# lcdInterface.net
KiCad netlist of a schematic drawn in EAGLE
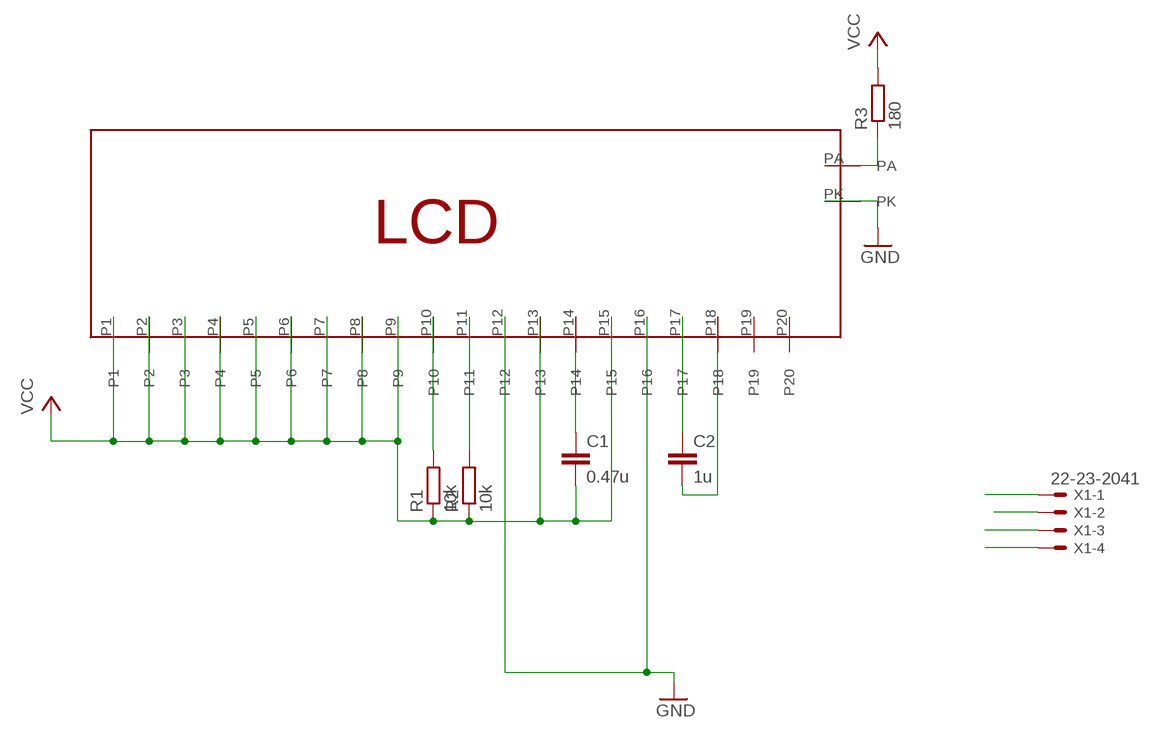
[diagram p0: schematic, sheet 1]

(export (version "E")
  (design (tool "Eeschema 10.0.6"))
  (components
    (comp (ref "C1")
      (value "0.47u")
      (footprint "eagle-import:C050-055X075")
      (libsource (lib "eagle-import") (part "C-EU050-055X075"))
    )
    (comp (ref "C2")
      (value "1u")
      (footprint "eagle-import:C050-030X075")
      (libsource (lib "eagle-import") (part "C-EU050-030X075"))
    )
    (comp (ref "R1")
      (value "10k")
      (footprint "eagle-import:0207_10")
      (libsource (lib "eagle-import") (part "R-EU_0207/10"))
    )
    (comp (ref "R2")
      (value "10k")
      (footprint "eagle-import:0207_10")
      (libsource (lib "eagle-import") (part "R-EU_0207/10"))
    )
    (comp (ref "R3")
      (value "180")
      (footprint "eagle-import:0207_10")
      (libsource (lib "eagle-import") (part "R-EU_0207/10"))
    )
    (comp (ref "U$1")
      (value "GE-01602F")
      (footprint "eagle-import:GE01602F")
      (libsource (lib "eagle-import") (part "GE-01602F"))
    )
    (comp (ref "X1")
      (value "22-23-2041")
      (footprint "eagle-import:22-23-2041")
      (fields (field (name "MF") "MOLEX"))
      (libsource (lib "eagle-import") (part "22-23-2041"))
    )
  )
  (nets
    (net (code "1") (name "/SCL") (class "Default")
      (node (ref "R1") (pin "2") (pinfunction "2_2") (pintype "passive"))
      (node (ref "U$1") (pin "P10") (pinfunction "P10_P10") (pintype "bidirectional"))
      (node (ref "X1") (pin "1") (pinfunction "S_1") (pintype "passive"))
    )
    (net (code "2") (name "/SDA") (class "Default")
      (node (ref "R2") (pin "2") (pinfunction "2_2") (pintype "passive"))
      (node (ref "U$1") (pin "P11") (pinfunction "P11_P11") (pintype "bidirectional"))
      (node (ref "X1") (pin "2") (pinfunction "S_2") (pintype "passive"))
    )
    (net (code "3") (name "GND") (class "Default")
      (node (ref "U$1") (pin "P12") (pinfunction "P12_P12") (pintype "bidirectional"))
      (node (ref "U$1") (pin "P16") (pinfunction "P16_P16") (pintype "bidirectional"))
      (node (ref "U$1") (pin "PK") (pinfunction "PK_PK") (pintype "bidirectional"))
      (node (ref "X1") (pin "4") (pinfunction "S_4") (pintype "passive"))
    )
    (net (code "4") (name "Net-(C1-Pad1)") (class "Default")
      (node (ref "C1") (pin "1") (pinfunction "1_1") (pintype "passive"))
      (node (ref "U$1") (pin "P14") (pinfunction "P14_P14") (pintype "bidirectional"))
    )
    (net (code "5") (name "Net-(C2-Pad1)") (class "Default")
      (node (ref "C2") (pin "1") (pinfunction "1_1") (pintype "passive"))
      (node (ref "U$1") (pin "P17") (pinfunction "P17_P17") (pintype "bidirectional"))
    )
    (net (code "6") (name "Net-(C2-Pad2)") (class "Default")
      (node (ref "C2") (pin "2") (pinfunction "2_2") (pintype "passive"))
      (node (ref "U$1") (pin "P18") (pinfunction "P18_P18") (pintype "bidirectional"))
    )
    (net (code "7") (name "Net-(R3-Pad1)") (class "Default")
      (node (ref "R3") (pin "1") (pinfunction "1_1") (pintype "passive"))
      (node (ref "U$1") (pin "PA") (pinfunction "PA_PA") (pintype "bidirectional"))
    )
    (net (code "8") (name "VCC") (class "Default")
      (node (ref "C1") (pin "2") (pinfunction "2_2") (pintype "passive"))
      (node (ref "R1") (pin "1") (pinfunction "1_1") (pintype "passive"))
      (node (ref "R2") (pin "1") (pinfunction "1_1") (pintype "passive"))
      (node (ref "R3") (pin "2") (pinfunction "2_2") (pintype "passive"))
      (node (ref "U$1") (pin "P1") (pinfunction "P1_P1") (pintype "bidirectional"))
      (node (ref "U$1") (pin "P13") (pinfunction "P13_P13") (pintype "bidirectional"))
      (node (ref "U$1") (pin "P15") (pinfunction "P15_P15") (pintype "bidirectional"))
      (node (ref "U$1") (pin "P2") (pinfunction "P2_P2") (pintype "bidirectional"))
      (node (ref "U$1") (pin "P3") (pinfunction "P3_P3") (pintype "bidirectional"))
      (node (ref "U$1") (pin "P4") (pinfunction "P4_P4") (pintype "bidirectional"))
      (node (ref "U$1") (pin "P5") (pinfunction "P5_P5") (pintype "bidirectional"))
      (node (ref "U$1") (pin "P6") (pinfunction "P6_P6") (pintype "bidirectional"))
      (node (ref "U$1") (pin "P7") (pinfunction "P7_P7") (pintype "bidirectional"))
      (node (ref "U$1") (pin "P8") (pinfunction "P8_P8") (pintype "bidirectional"))
      (node (ref "U$1") (pin "P9") (pinfunction "P9_P9") (pintype "bidirectional"))
      (node (ref "X1") (pin "3") (pinfunction "S_3") (pintype "passive"))
    )
    (net (code "9") (name "unconnected-(U$1-PadP19)") (class "Default")
      (node (ref "U$1") (pin "P19") (pinfunction "P19_P19") (pintype "bidirectional"))
    )
    (net (code "10") (name "unconnected-(U$1-PadP20)") (class "Default")
      (node (ref "U$1") (pin "P20") (pinfunction "P20_P20") (pintype "bidirectional"))
    )
  )
)
